# Nolia_LCD.net
KiCad netlist of a schematic drawn in Altium Designer
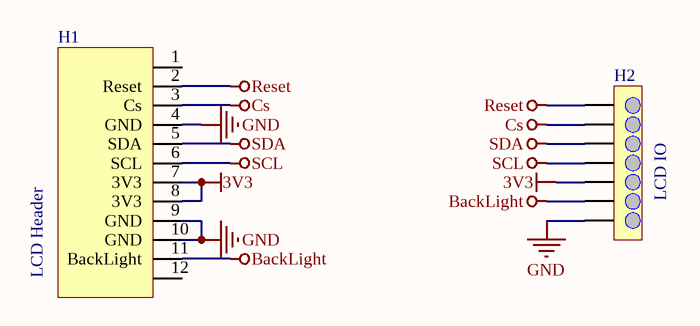
[diagram p0: Nolia LCD.SchDoc]

(export (version "E")
  (design (tool "Eeschema 10.0.6"))
  (components
    (comp (ref "H1")
      (value "LCD Header 12*1")
      (footprint "LCD Header - duplicate")
      (fields (field (name "ALTIUM_UNNAMED_3") "LCD Header"))
      (libsource (lib "LCD Header") (part "LCD Header 12*1"))
    )
    (comp (ref "H2") (value "LCD IO") (footprint "HEADER 7X1") (libsource (lib "3D LIB") (part "HEDER 7PIN")))
  )
  (nets
    (net (code "1") (name "3V3") (class "Default")
      (node (ref "H1") (pin "7") (pinfunction "3V3_7") (pintype "passive"))
      (node (ref "H1") (pin "8") (pinfunction "3V3_8") (pintype "passive"))
      (node (ref "H2") (pin "3") (pinfunction "H_3") (pintype "passive"))
    )
    (net (code "2") (name "BackLight") (class "Default")
      (node (ref "H1") (pin "11") (pinfunction "BackLight_11") (pintype "passive"))
      (node (ref "H2") (pin "2") (pinfunction "H_2") (pintype "passive"))
    )
    (net (code "3") (name "Cs") (class "Default")
      (node (ref "H1") (pin "3") (pinfunction "Cs_3") (pintype "passive"))
      (node (ref "H2") (pin "6") (pinfunction "H_6") (pintype "passive"))
    )
    (net (code "4") (name "GND") (class "Default")
      (node (ref "H1") (pin "10") (pinfunction "GND_10") (pintype "passive"))
      (node (ref "H1") (pin "4") (pinfunction "GND_4") (pintype "passive"))
      (node (ref "H1") (pin "9") (pinfunction "GND_9") (pintype "passive"))
      (node (ref "H2") (pin "1") (pinfunction "H_1") (pintype "passive"))
    )
    (net (code "5") (name "Reset") (class "Default")
      (node (ref "H1") (pin "2") (pinfunction "Reset_2") (pintype "passive"))
      (node (ref "H2") (pin "7") (pinfunction "H_7") (pintype "passive"))
    )
    (net (code "6") (name "SCL") (class "Default")
      (node (ref "H1") (pin "6") (pinfunction "SCL_6") (pintype "passive"))
      (node (ref "H2") (pin "4") (pinfunction "H_4") (pintype "passive"))
    )
    (net (code "7") (name "SDA") (class "Default")
      (node (ref "H1") (pin "5") (pinfunction "SDA_5") (pintype "passive"))
      (node (ref "H2") (pin "5") (pinfunction "H_5") (pintype "passive"))
    )
    (net (code "8") (name "unconnected-(H1-Pad1)") (class "Default")
      (node (ref "H1") (pin "1") (pintype "passive"))
    )
    (net (code "9") (name "unconnected-(H1-Pad12)") (class "Default")
      (node (ref "H1") (pin "12") (pintype "passive"))
    )
  )
)
